# eins.net
KiCad netlist of a schematic drawn in EAGLE
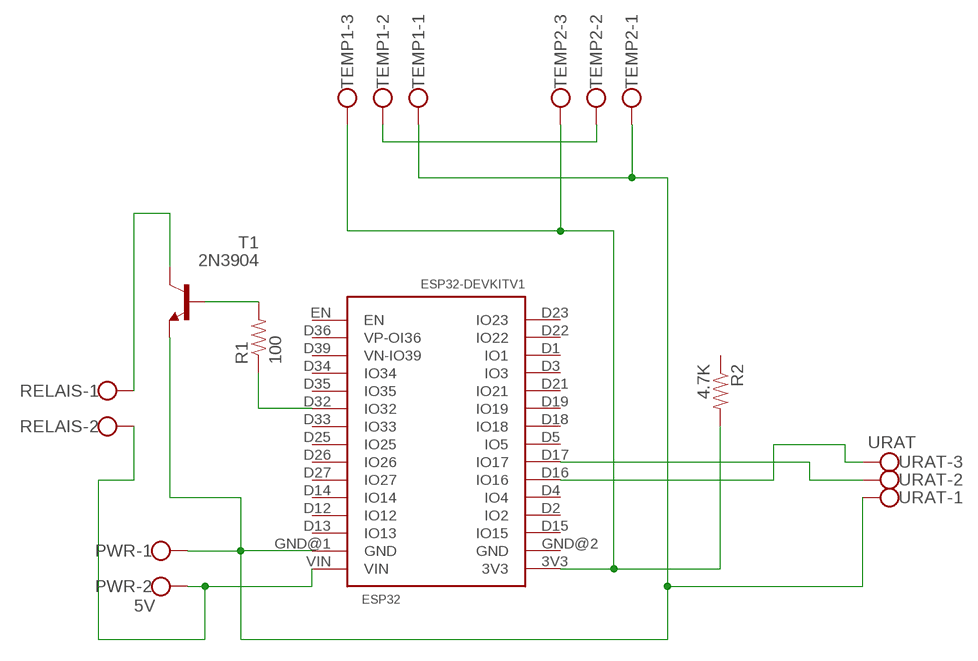
[diagram p0: schematic, sheet 1]

(export (version "E")
  (design (tool "Eeschema 10.0.6"))
  (components
    (comp (ref "ESP32")
      (value "ESP32DEVKITV1")
      (footprint "eagle-import:ESP32-DEVKITV1")
      (libsource (lib "eagle-import") (part "ESP32DEVKITV1"))
    )
    (comp (ref "PWR")
      (value "5V")
      (footprint "eagle-import:W237-102")
      (fields (field (name "MPN") "237-102"))
      (libsource (lib "eagle-import") (part "W237-102"))
    )
    (comp (ref "R1")
      (value "100")
      (footprint "eagle-import:AXIAL-0.4")
      (libsource (lib "eagle-import") (part "RESISTORPTH-1/4W"))
    )
    (comp (ref "R2")
      (value "4.7K")
      (footprint "eagle-import:AXIAL-0.4")
      (libsource (lib "eagle-import") (part "RESISTORPTH-1/4W"))
    )
    (comp (ref "RELAIS")
      (value "W237-102")
      (footprint "eagle-import:W237-102")
      (fields (field (name "MPN") "237-102"))
      (libsource (lib "eagle-import") (part "W237-102"))
    )
    (comp (ref "T1")
      (value "2N3904")
      (footprint "eagle-import:TO92")
      (libsource (lib "eagle-import") (part "2N3904"))
    )
    (comp (ref "TEMP1")
      (value "W237-103")
      (footprint "eagle-import:W237-103")
      (fields (field (name "MPN") "237-103"))
      (libsource (lib "eagle-import") (part "W237-103"))
    )
    (comp (ref "TEMP2")
      (value "W237-103")
      (footprint "eagle-import:W237-103")
      (fields (field (name "MPN") "237-103"))
      (libsource (lib "eagle-import") (part "W237-103"))
    )
    (comp (ref "URAT")
      (value "URAT")
      (footprint "eagle-import:W237-103")
      (fields (field (name "MPN") "237-103"))
      (libsource (lib "eagle-import") (part "W237-103"))
    )
  )
  (nets
    (net (code "1") (name "Net-(ESP32-IO16)") (class "Default")
      (node (ref "ESP32") (pin "D16") (pinfunction "IO16_D16") (pintype "bidirectional"))
      (node (ref "URAT") (pin "3") (pinfunction "KL_3") (pintype "passive"))
    )
    (net (code "2") (name "Net-(ESP32-IO17)") (class "Default")
      (node (ref "ESP32") (pin "D17") (pinfunction "IO17_D17") (pintype "bidirectional"))
      (node (ref "URAT") (pin "2") (pinfunction "KL_2") (pintype "passive"))
    )
    (net (code "3") (name "Net-(ESP32-IO32)") (class "Default")
      (node (ref "ESP32") (pin "D32") (pinfunction "IO32_D32") (pintype "bidirectional"))
      (node (ref "R1") (pin "P$1") (pinfunction "1_P$1") (pintype "passive"))
    )
    (net (code "4") (name "Net-(PWRA-KL)") (class "Default")
      (node (ref "ESP32") (pin "GND@1") (pinfunction "GND_GND@1") (pintype "bidirectional"))
      (node (ref "PWR") (pin "1") (pinfunction "KL_1") (pintype "passive"))
      (node (ref "T1") (pin "3") (pinfunction "E_3") (pintype "passive"))
      (node (ref "TEMP1") (pin "1") (pinfunction "KL_1") (pintype "passive"))
      (node (ref "TEMP2") (pin "1") (pinfunction "KL_1") (pintype "passive"))
      (node (ref "URAT") (pin "1") (pinfunction "KL_1") (pintype "passive"))
    )
    (net (code "5") (name "Net-(PWRB-KL)") (class "Default")
      (node (ref "ESP32") (pin "VIN") (pinfunction "VIN_VIN") (pintype "bidirectional"))
      (node (ref "PWR") (pin "2") (pinfunction "KL_2") (pintype "passive"))
      (node (ref "RELAIS") (pin "2") (pinfunction "KL_2") (pintype "passive"))
    )
    (net (code "6") (name "Net-(R1-2)") (class "Default")
      (node (ref "R1") (pin "P$2") (pinfunction "2_P$2") (pintype "passive"))
      (node (ref "T1") (pin "2") (pinfunction "B_2") (pintype "passive"))
    )
    (net (code "7") (name "Net-(R2-2)") (class "Default")
      (node (ref "ESP32") (pin "3V3") (pinfunction "3V3_3V3") (pintype "bidirectional"))
      (node (ref "R2") (pin "P$2") (pinfunction "2_P$2") (pintype "passive"))
      (node (ref "TEMP1") (pin "3") (pinfunction "KL_3") (pintype "passive"))
      (node (ref "TEMP2") (pin "3") (pinfunction "KL_3") (pintype "passive"))
    )
    (net (code "8") (name "Net-(RELAISA-KL)") (class "Default")
      (node (ref "RELAIS") (pin "1") (pinfunction "KL_1") (pintype "passive"))
      (node (ref "T1") (pin "1") (pinfunction "C_1") (pintype "passive"))
    )
    (net (code "9") (name "Net-(TEMP1B-KL)") (class "Default")
      (node (ref "TEMP1") (pin "2") (pinfunction "KL_2") (pintype "passive"))
      (node (ref "TEMP2") (pin "2") (pinfunction "KL_2") (pintype "passive"))
    )
    (net (code "10") (name "unconnected-(ESP32-GND-PadGND@2)") (class "Default")
      (node (ref "ESP32") (pin "GND@2") (pinfunction "GND_GND@2") (pintype "bidirectional"))
    )
    (net (code "11") (name "unconnected-(ESP32-IO1-PadD1)") (class "Default")
      (node (ref "ESP32") (pin "D1") (pinfunction "IO1_D1") (pintype "bidirectional"))
    )
    (net (code "12") (name "unconnected-(ESP32-IO2-PadD2)") (class "Default")
      (node (ref "ESP32") (pin "D2") (pinfunction "IO2_D2") (pintype "bidirectional"))
    )
    (net (code "13") (name "unconnected-(ESP32-IO3-PadD3)") (class "Default")
      (node (ref "ESP32") (pin "D3") (pinfunction "IO3_D3") (pintype "bidirectional"))
    )
    (net (code "14") (name "unconnected-(ESP32-IO4-PadD4)") (class "Default")
      (node (ref "ESP32") (pin "D4") (pinfunction "IO4_D4") (pintype "bidirectional"))
    )
    (net (code "15") (name "unconnected-(ESP32-IO5-PadD5)") (class "Default")
      (node (ref "ESP32") (pin "D5") (pinfunction "IO5_D5") (pintype "bidirectional"))
    )
    (net (code "16") (name "unconnected-(ESP32-IO12-PadD12)") (class "Default")
      (node (ref "ESP32") (pin "D12") (pinfunction "IO12_D12") (pintype "bidirectional"))
    )
    (net (code "17") (name "unconnected-(ESP32-IO13-PadD13)") (class "Default")
      (node (ref "ESP32") (pin "D13") (pinfunction "IO13_D13") (pintype "bidirectional"))
    )
    (net (code "18") (name "unconnected-(ESP32-IO14-PadD14)") (class "Default")
      (node (ref "ESP32") (pin "D14") (pinfunction "IO14_D14") (pintype "bidirectional"))
    )
    (net (code "19") (name "unconnected-(ESP32-IO15-PadD15)") (class "Default")
      (node (ref "ESP32") (pin "D15") (pinfunction "IO15_D15") (pintype "bidirectional"))
    )
    (net (code "20") (name "unconnected-(ESP32-IO18-PadD18)") (class "Default")
      (node (ref "ESP32") (pin "D18") (pinfunction "IO18_D18") (pintype "bidirectional"))
    )
    (net (code "21") (name "unconnected-(ESP32-IO19-PadD19)") (class "Default")
      (node (ref "ESP32") (pin "D19") (pinfunction "IO19_D19") (pintype "bidirectional"))
    )
    (net (code "22") (name "unconnected-(ESP32-IO21-PadD21)") (class "Default")
      (node (ref "ESP32") (pin "D21") (pinfunction "IO21_D21") (pintype "bidirectional"))
    )
    (net (code "23") (name "unconnected-(ESP32-IO22-PadD22)") (class "Default")
      (node (ref "ESP32") (pin "D22") (pinfunction "IO22_D22") (pintype "bidirectional"))
    )
    (net (code "24") (name "unconnected-(ESP32-IO23-PadD23)") (class "Default")
      (node (ref "ESP32") (pin "D23") (pinfunction "IO23_D23") (pintype "bidirectional"))
    )
    (net (code "25") (name "unconnected-(ESP32-IO25-PadD25)") (class "Default")
      (node (ref "ESP32") (pin "D25") (pinfunction "IO25_D25") (pintype "bidirectional"))
    )
    (net (code "26") (name "unconnected-(ESP32-IO26-PadD26)") (class "Default")
      (node (ref "ESP32") (pin "D26") (pinfunction "IO26_D26") (pintype "bidirectional"))
    )
    (net (code "27") (name "unconnected-(ESP32-IO27-PadD27)") (class "Default")
      (node (ref "ESP32") (pin "D27") (pinfunction "IO27_D27") (pintype "bidirectional"))
    )
    (net (code "28") (name "unconnected-(ESP32-IO33-PadD33)") (class "Default")
      (node (ref "ESP32") (pin "D33") (pinfunction "IO33_D33") (pintype "bidirectional"))
    )
    (net (code "29") (name "unconnected-(ESP32-IO34-PadD34)") (class "Default")
      (node (ref "ESP32") (pin "D34") (pinfunction "IO34_D34") (pintype "bidirectional"))
    )
    (net (code "30") (name "unconnected-(ESP32-IO35-PadD35)") (class "Default")
      (node (ref "ESP32") (pin "D35") (pinfunction "IO35_D35") (pintype "bidirectional"))
    )
    (net (code "31") (name "unconnected-(ESP32-PadEN)") (class "Default")
      (node (ref "ESP32") (pin "EN") (pinfunction "EN_EN") (pintype "bidirectional"))
    )
    (net (code "32") (name "unconnected-(ESP32-VN-IO39-PadD39)") (class "Default")
      (node (ref "ESP32") (pin "D39") (pinfunction "VN-IO39_D39") (pintype "bidirectional"))
    )
    (net (code "33") (name "unconnected-(ESP32-VP-OI36-PadD36)") (class "Default")
      (node (ref "ESP32") (pin "D36") (pinfunction "VP-OI36_D36") (pintype "bidirectional"))
    )
    (net (code "34") (name "unconnected-(R2-1-PadP$1)") (class "Default")
      (node (ref "R2") (pin "P$1") (pinfunction "1_P$1") (pintype "passive"))
    )
  )
)
